# ProProject_TC264__2024-10-06.net
KiCad netlist of a schematic drawn in EasyEDA Pro
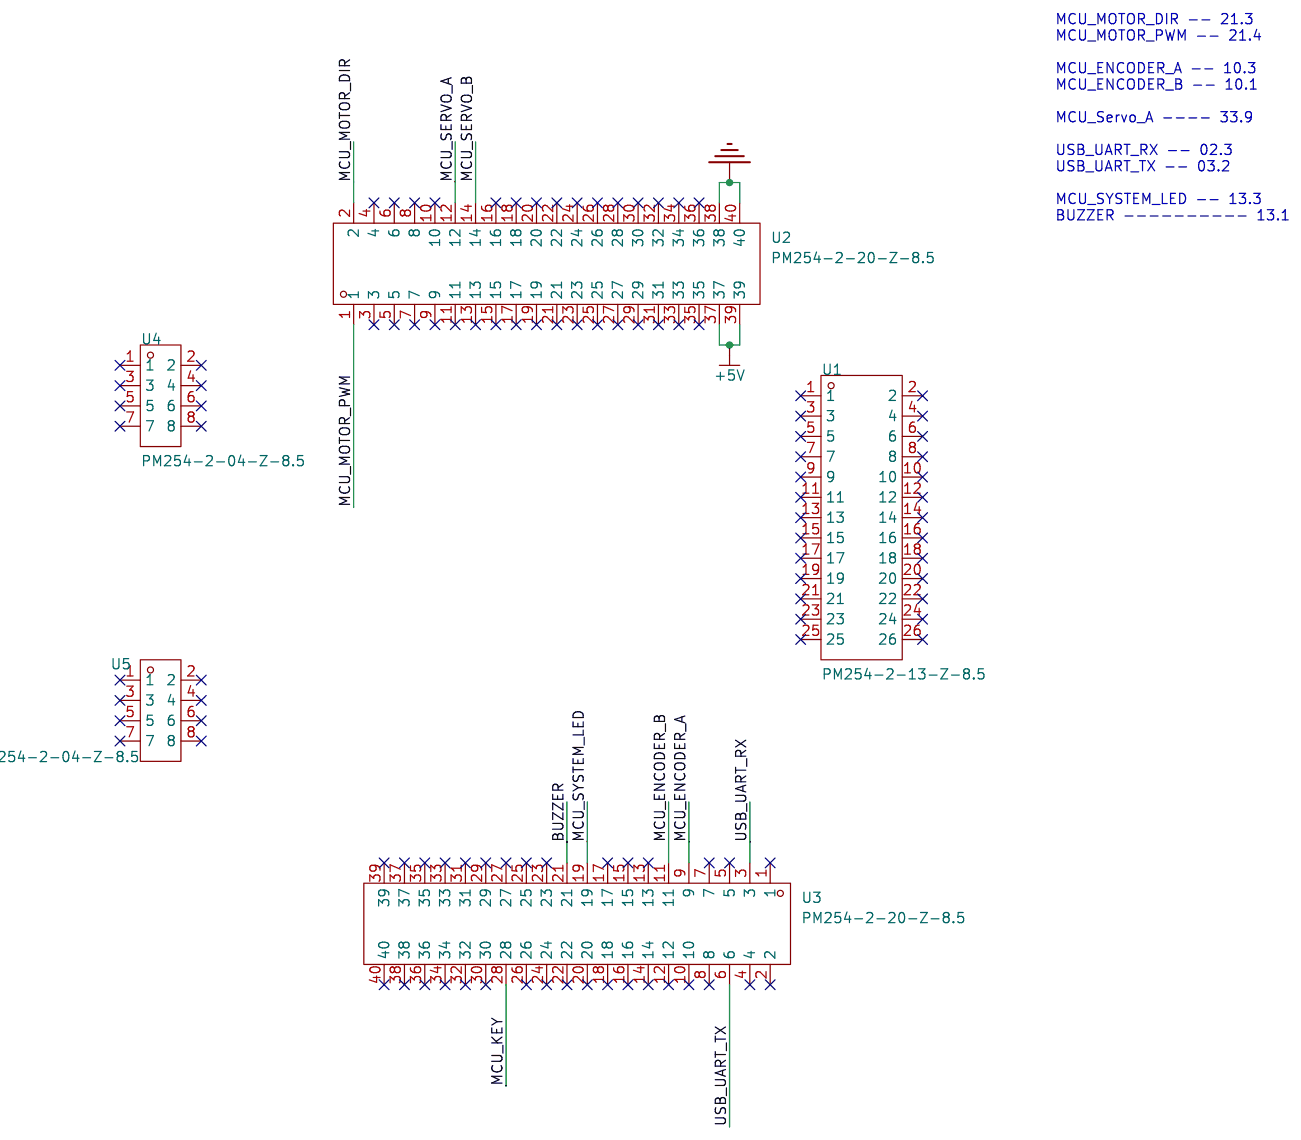
[diagram p0: CoreBoard]
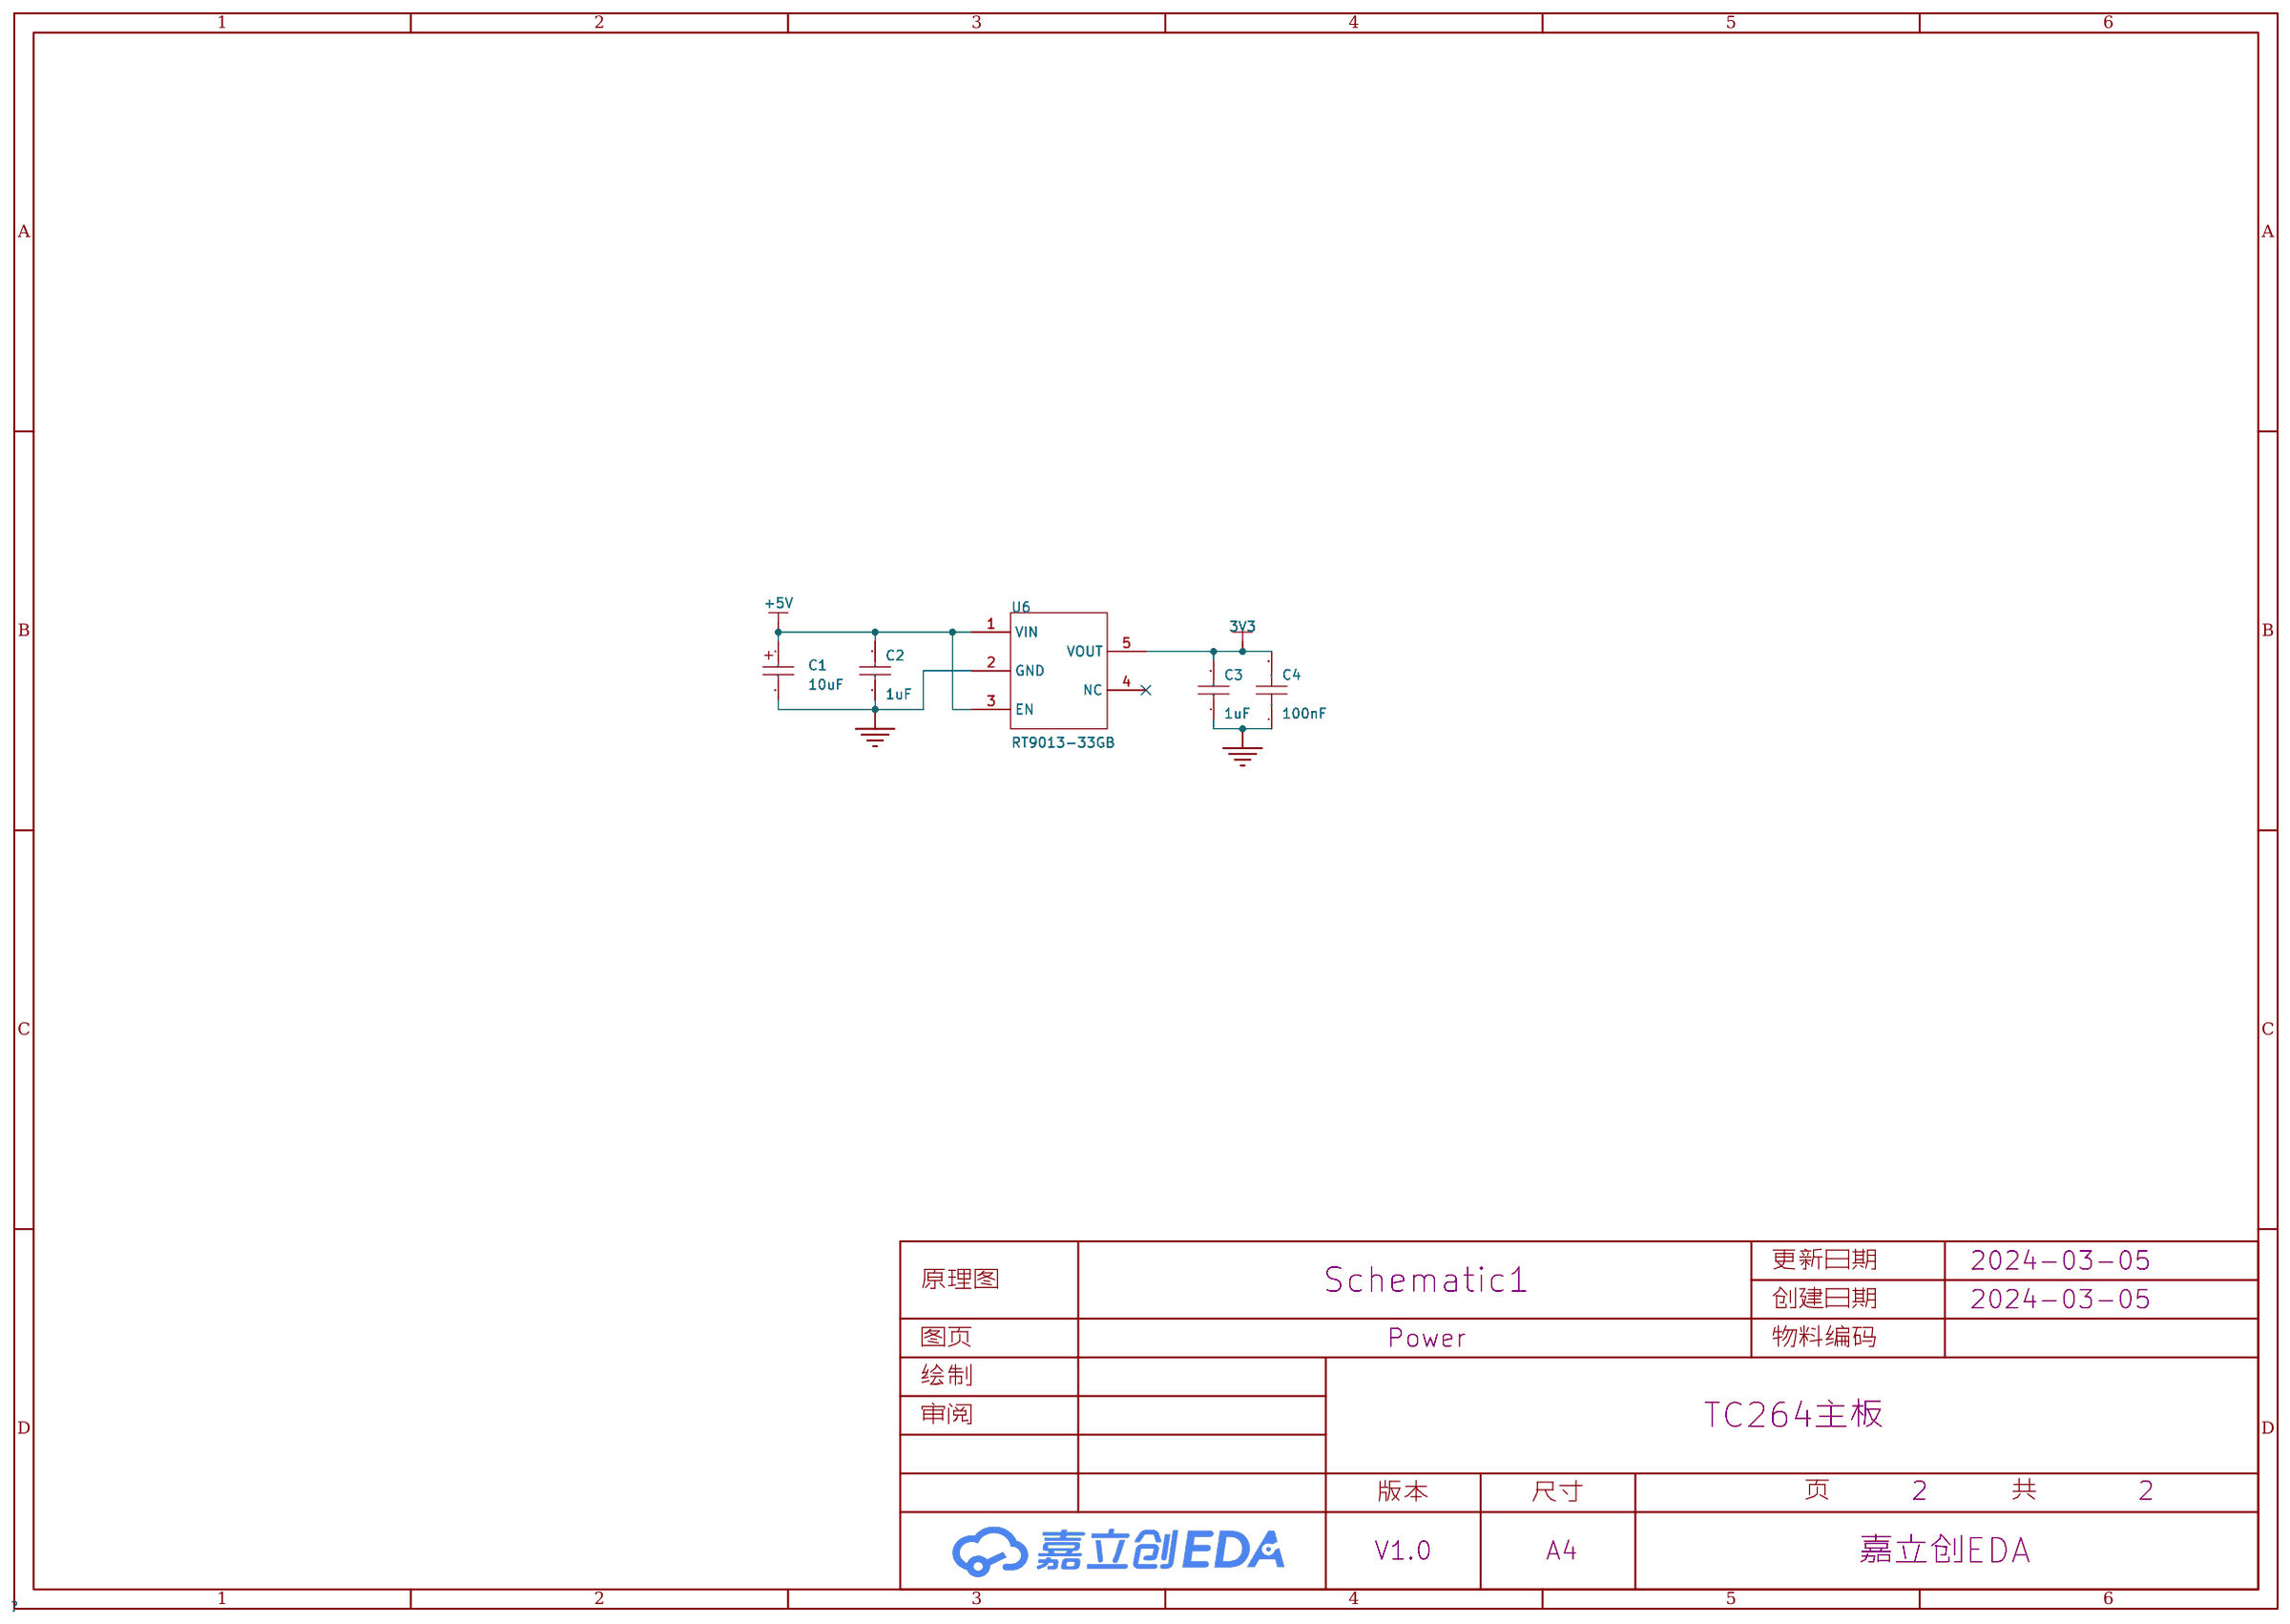
[diagram p1: Power]
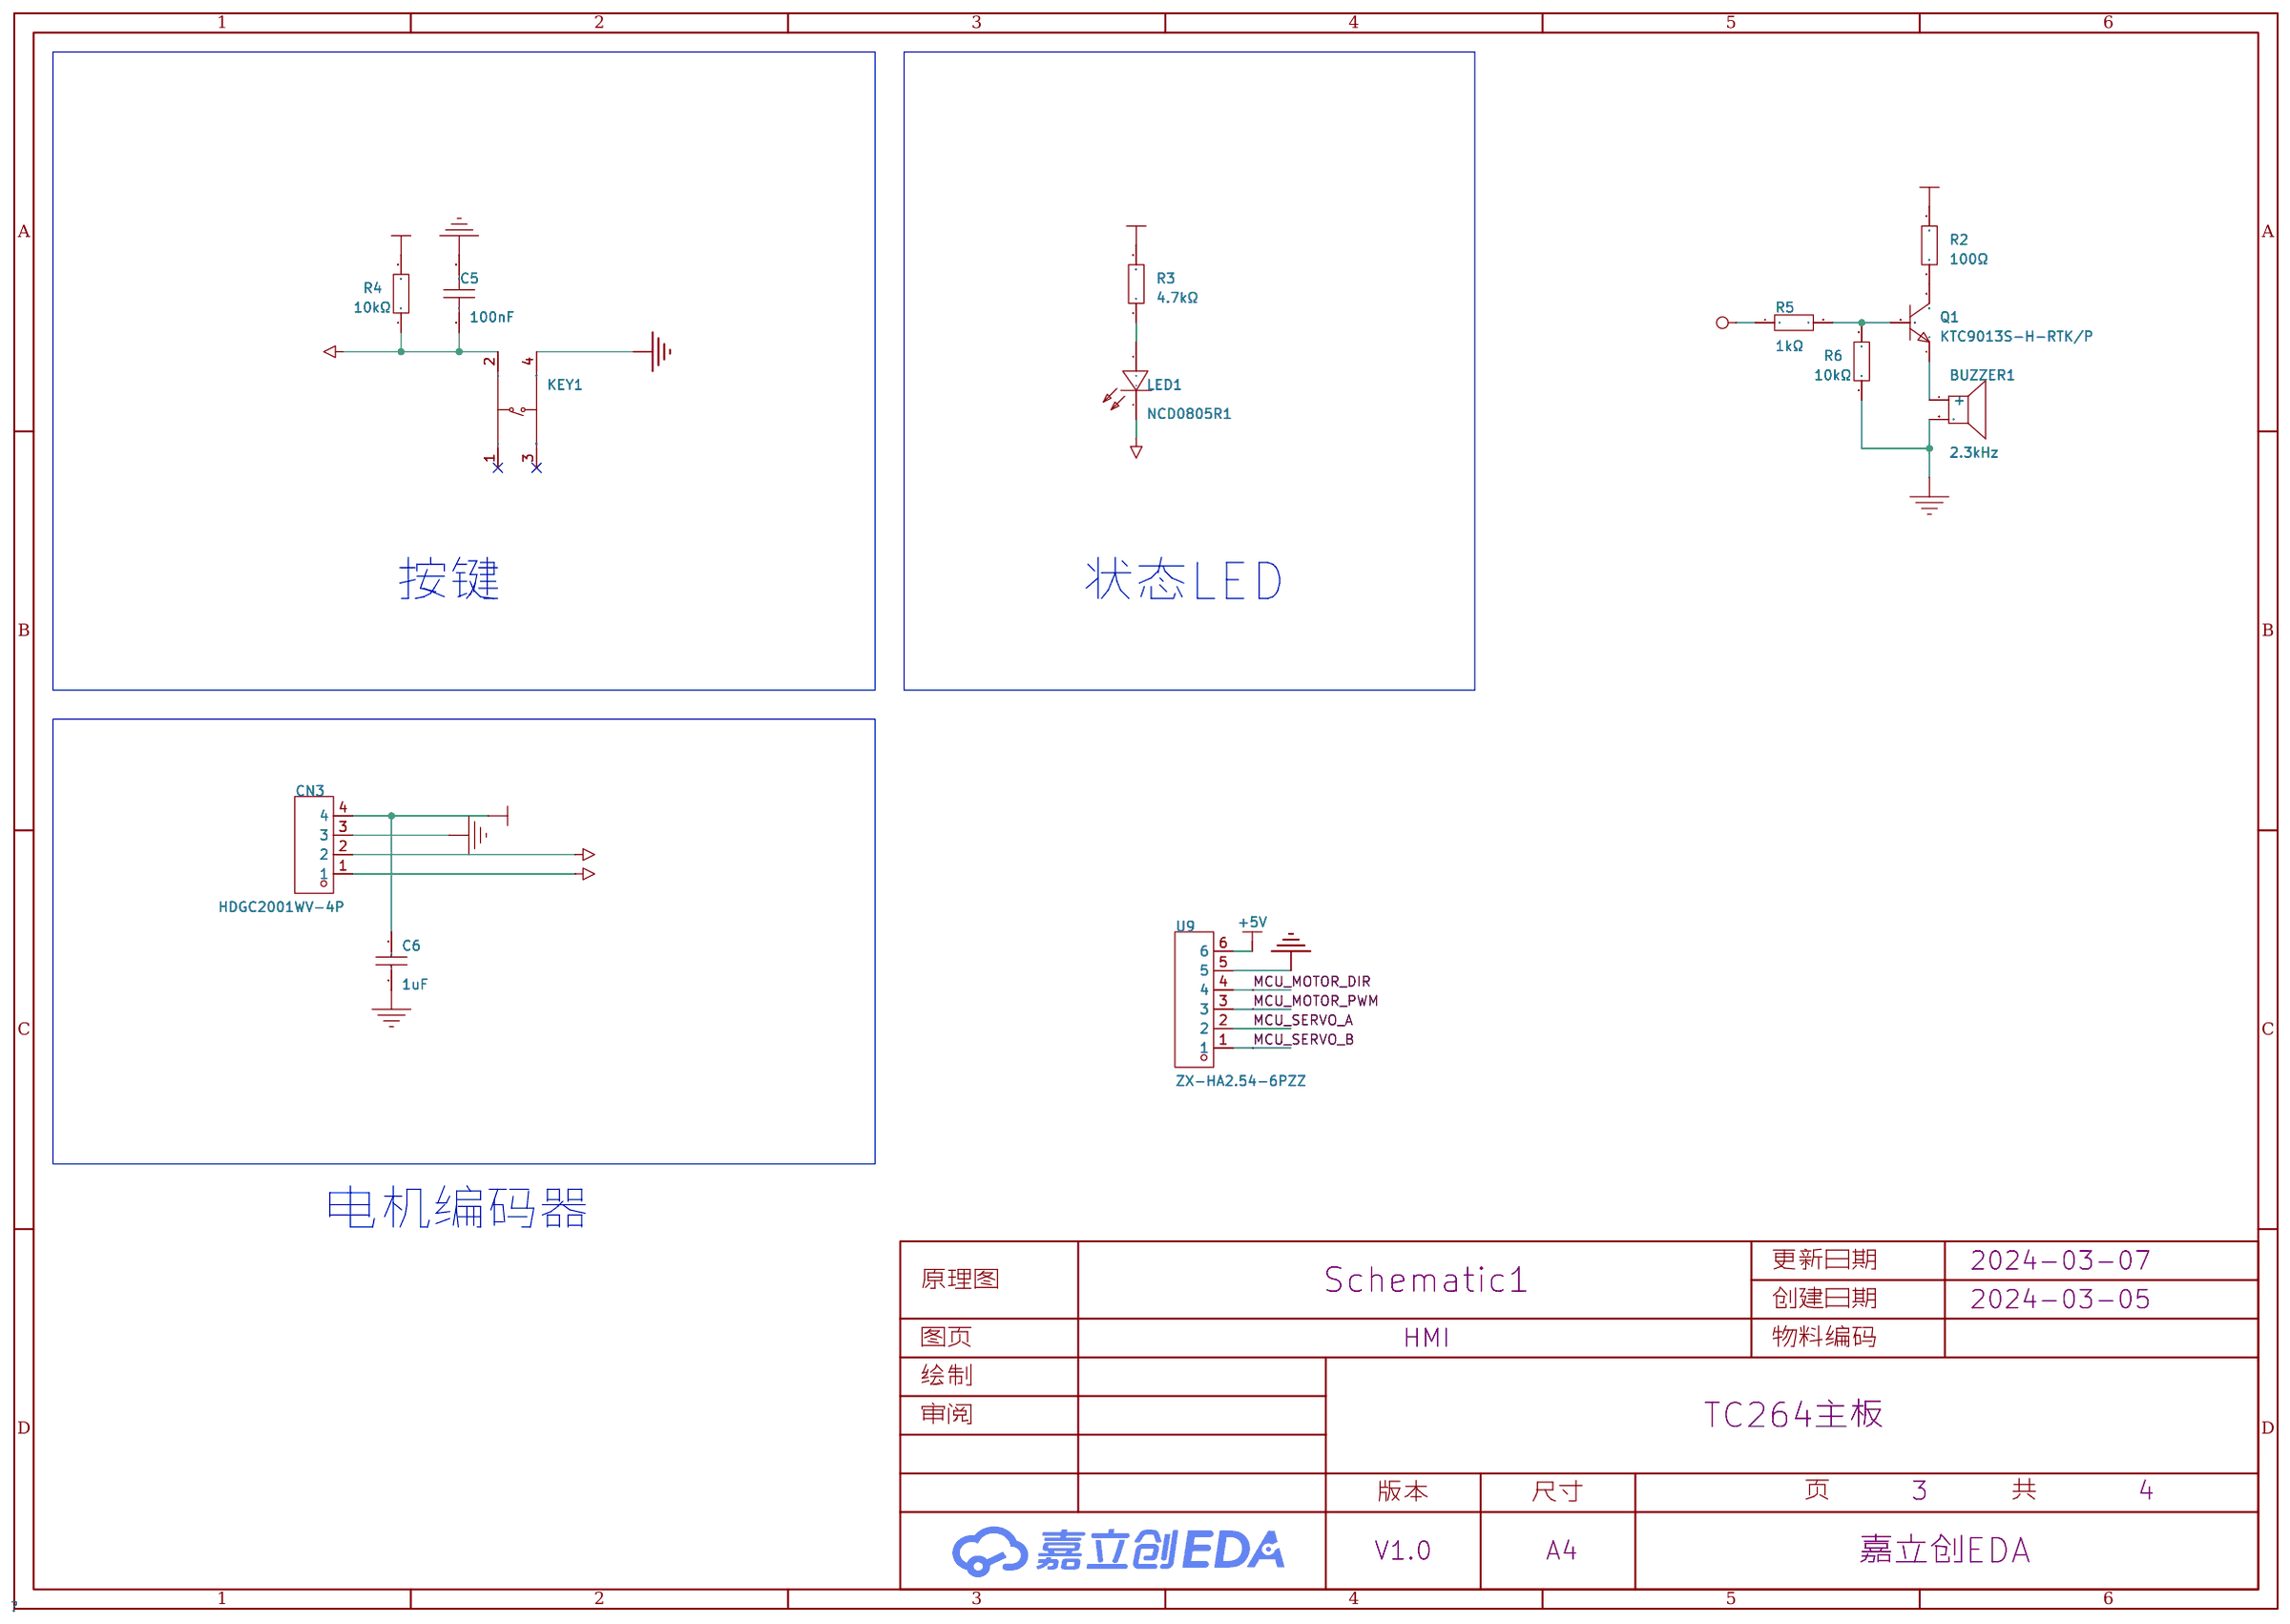
[diagram p2: HMI]
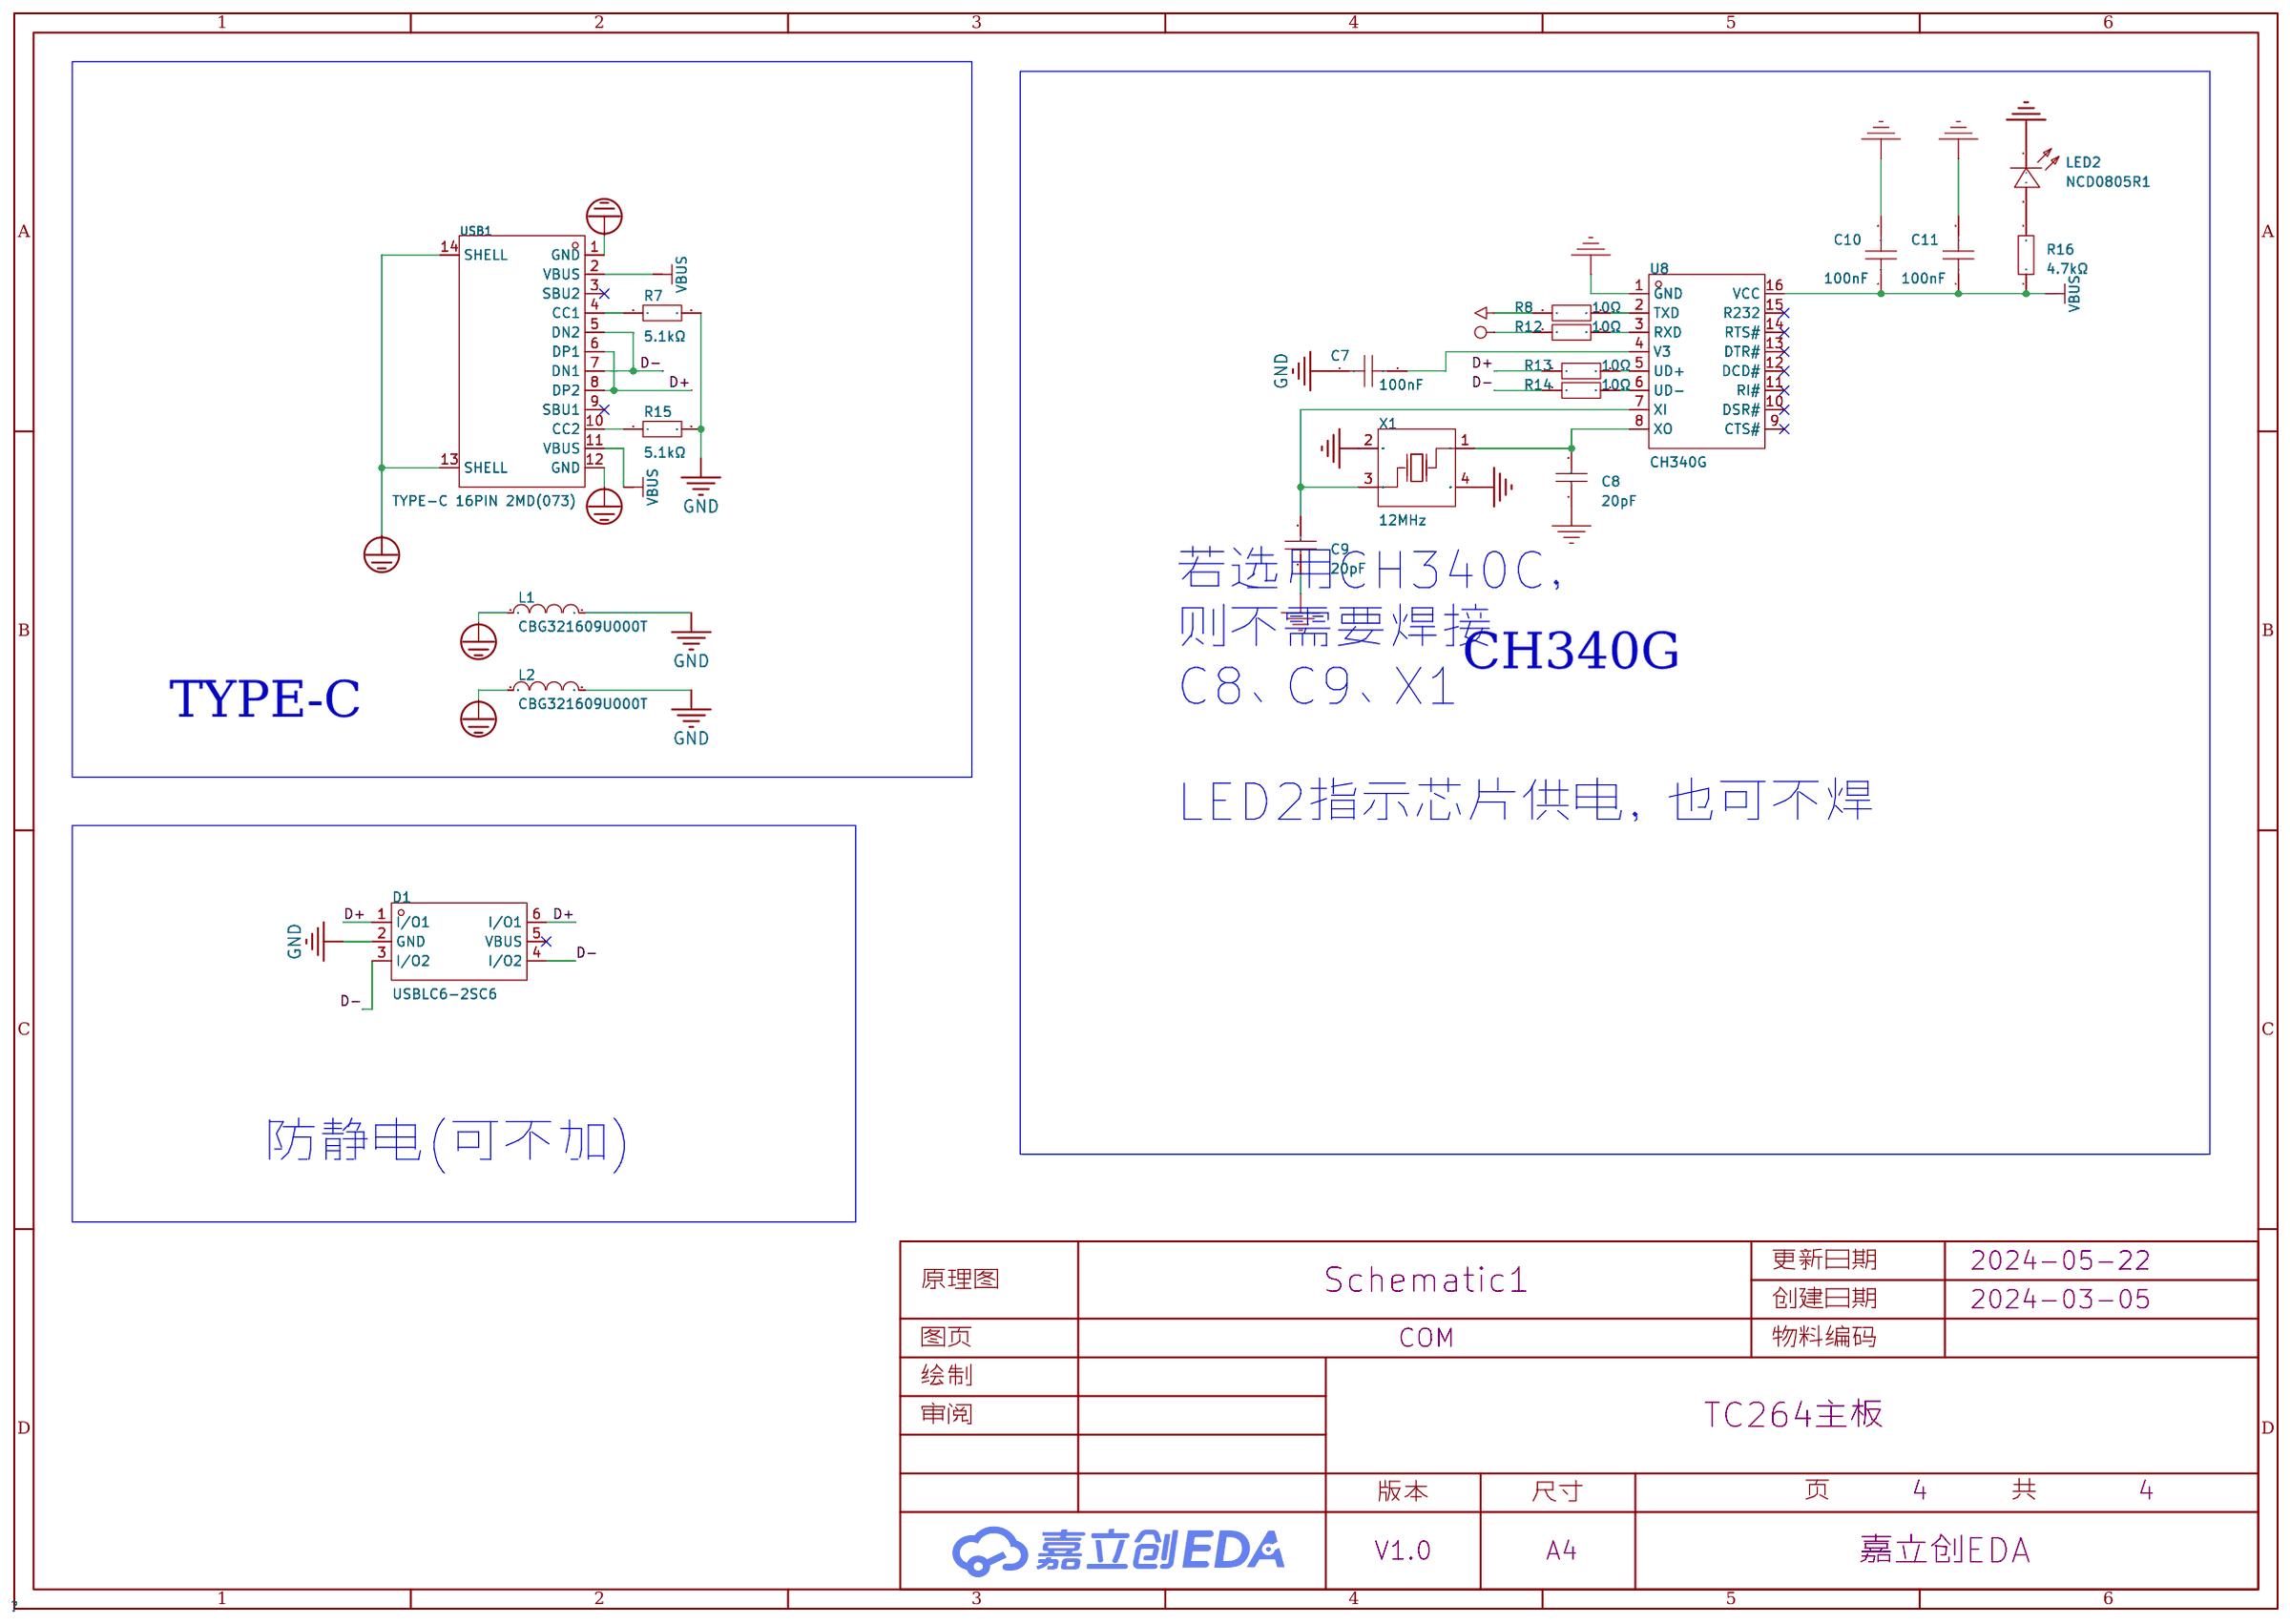
[diagram p3: COM]

(export (version "E")
  (design (tool "Eeschema 10.0.6"))
  (components
    (comp (ref "U1")
      (value "PM254-2-13-Z-8.5")
      (footprint "easyedapro:HDR-TH_26P-P2.54-V-F-R2-C13-S2.54-1")
      (fields (field (name "Manufacturer") "HCTL(华灿天禄)"))
      (libsource (lib "easyedapro") (part "PM254-2-13-Z-8.5"))
    )
    (comp (ref "U2")
      (value "PM254-2-20-Z-8.5")
      (footprint "easyedapro:HDR-TH_40P-P2.54-V-F-R2-C20-S2.54")
      (fields (field (name "Manufacturer") "HCTL(华灿天禄)"))
      (libsource (lib "easyedapro") (part "PM254-2-20-Z-8.5"))
    )
    (comp (ref "U3")
      (value "PM254-2-20-Z-8.5")
      (footprint "easyedapro:HDR-TH_40P-P2.54-V-F-R2-C20-S2.54")
      (fields (field (name "Manufacturer") "HCTL(华灿天禄)"))
      (libsource (lib "easyedapro") (part "PM254-2-20-Z-8.5"))
    )
    (comp (ref "U4")
      (value "PM254-2-04-Z-8.5")
      (footprint "easyedapro:HDR-TH_8P-P2.54-V-F-R2-C4-S2.54")
      (fields (field (name "Manufacturer") "HCTL(华灿天禄)"))
      (libsource (lib "easyedapro") (part "PM254-2-04-Z-8.5"))
    )
    (comp (ref "U5")
      (value "PM254-2-04-Z-8.5")
      (footprint "easyedapro:HDR-TH_8P-P2.54-V-F-R2-C4-S2.54")
      (fields (field (name "Manufacturer") "HCTL(华灿天禄)"))
      (libsource (lib "easyedapro") (part "PM254-2-04-Z-8.5"))
    )
    (comp (ref "C1")
      (value "10uF")
      (footprint "easyedapro:CAP-SMD_L3.2-W1.6-RD-C7171")
      (description "容值:10uF;精度:±10%;额定电压:16V;等效串联电阻:3Ω@100kHz;")
      (fields (field (name "Manufacturer Part") "TAJA106K016RNJ") (field (name "Manufacturer") "Kyocera AVX"))
      (libsource (lib "easyedapro") (part "TAJA106K016RNJ"))
    )
    (comp (ref "C2")
      (value "1uF")
      (footprint "easyedapro:C0603")
      (description "容值:1uF;精度:±10%;额定电压:25V;材质(温度系数):X7R;")
      (fields (field (name "Manufacturer Part") "0603B105K250NT") (field (name "Manufacturer") "FH(风华)"))
      (libsource (lib "easyedapro") (part "0603B105K250NT"))
    )
    (comp (ref "C3")
      (value "1uF")
      (footprint "easyedapro:C0603")
      (description "容值:1uF;精度:±10%;额定电压:25V;材质(温度系数):X7R;")
      (fields (field (name "Manufacturer Part") "0603B105K250NT") (field (name "Manufacturer") "FH(风华)"))
      (libsource (lib "easyedapro") (part "0603B105K250NT"))
    )
    (comp (ref "C4")
      (value "100nF")
      (footprint "easyedapro:C0603")
      (description "容值:100nF;精度:±10%;额定电压:50V;材质(温度系数):X7R;")
      (fields
        (field (name "Manufacturer Part") "CC0603KRX7R9BB104")
        (field (name "Manufacturer") "YAGEO(国巨)")
      )
      (libsource (lib "easyedapro") (part "CC0603KRX7R9BB104"))
    )
    (comp (ref "U6")
      (value "RT9013-33GB")
      (footprint "easyedapro:SOT-23-5_L3.0-W1.7-P0.95-LS2.8-BL")
      (description "输出类型:固定;最大输入电压:5.5V;输出电压:3.3V;最大输出电流:500mA;电源纹波抑制比(PSRR):50dB@(10kHz);输出极性:正极;")
      (fields (field (name "Manufacturer") "RICHTEK(立锜)"))
      (libsource (lib "easyedapro") (part "RT9013-33GB"))
    )
    (comp (ref "BUZZER1")
      (value "2.3kHz")
      (footprint "easyedapro:BUZ-TH_BD12.0-P7.60-D0.6-FD")
      (description "驱动方式:有源(内含驱动线路);构造类型:电磁式;额定电压:5V;频率:2.3kHz;声压(SPL):85dB@5V,10cm;")
      (fields (field (name "Manufacturer Part") "TMB12A05") (field (name "Manufacturer") "华能"))
      (libsource (lib "easyedapro") (part "TMB12A05"))
    )
    (comp (ref "C5")
      (value "100nF")
      (footprint "easyedapro:C0603")
      (description "容值:100nF;精度:±10%;额定电压:50V;材质(温度系数):X7R;")
      (fields
        (field (name "Manufacturer Part") "CC0603KRX7R9BB104")
        (field (name "Manufacturer") "YAGEO(国巨)")
      )
      (libsource (lib "easyedapro") (part "CC0603KRX7R9BB104"))
    )
    (comp (ref "C6")
      (value "1uF")
      (footprint "easyedapro:C0603")
      (description "容值:1uF;精度:±10%;额定电压:25V;材质(温度系数):X7R;")
      (fields (field (name "Manufacturer Part") "0603B105K250NT") (field (name "Manufacturer") "FH(风华)"))
      (libsource (lib "easyedapro") (part "0603B105K250NT"))
    )
    (comp (ref "CN3")
      (value "HDGC2001WV-4P")
      (footprint "easyedapro:CONN-TH_4P-P2.00_HDGC_HDGC2001WV-4P")
      (fields (field (name "Manufacturer") "HDGC(华德共创)"))
      (libsource (lib "easyedapro") (part "HDGC2001WV-4P"))
    )
    (comp (ref "KEY1")
      (value "TS665CJ")
      (footprint "easyedapro:SW-TH_4P-L6.0-W6.0-P4.50-LS6.5")
      (description "触点电流:50mA;额定电压(DC):12V;电路结构:单刀单掷;安装方式:直插;按钮形状:圆形按钮;带灯:-;开关长度:6mm;开关宽度:6mm;开关高度:5mm;")
      (fields (field (name "Manufacturer") "SHOU HAN(首韩)"))
      (libsource (lib "easyedapro") (part "TS665CJ"))
    )
    (comp (ref "LED1")
      (value "NCD0805R1")
      (footprint "easyedapro:LED0805-RD")
      (description "发光颜色:红灯;")
      (fields (field (name "Manufacturer") "国星光电"))
      (libsource (lib "easyedapro") (part "FC-2012HRK-620D"))
    )
    (comp (ref "Q1")
      (value "KTC9013S-H-RTK/P")
      (footprint "easyedapro:SOT-23-3_L2.9-W1.3-P1.90-LS2.4-TR-CW")
      (fields (field (name "Manufacturer") "KEC"))
      (libsource (lib "easyedapro") (part "KTC9013S-H-RTK/P"))
    )
    (comp (ref "R2")
      (value "100Ω")
      (footprint "easyedapro:R0603")
      (description "电阻类型:厚膜电阻;阻值:100Ω;精度:±1%;功率:100mW;温度系数:±200ppm/°C;最大工作电压:75V;工作温度范围:-55°C~+155°C;")
      (fields
        (field (name "Manufacturer Part") "0603WAF1000T5E")
        (field (name "Manufacturer") "UNI-ROYAL(厚声)")
      )
      (libsource (lib "easyedapro") (part "0603WAF1000T5E"))
    )
    (comp (ref "R3")
      (value "4.7kΩ")
      (footprint "easyedapro:R0805")
      (description "阻值:4.7kΩ;精度:±1%;功率:125mW;温度系数:±100ppm/°C;最大工作电压:150V;工作温度范围:-55°C~+155°C;")
      (fields (field (name "Manufacturer Part") "RS-05K4701FT") (field (name "Manufacturer") "FH(风华)"))
      (libsource (lib "easyedapro") (part "RS-05K4701FT"))
    )
    (comp (ref "R4")
      (value "10kΩ")
      (footprint "easyedapro:R0603")
      (description "电阻类型:厚膜电阻;阻值:10kΩ;精度:±1%;功率:100mW;温度系数:±100ppm/°C;最大工作电压:75V;工作温度范围:-55°C~+155°C;")
      (fields
        (field (name "Manufacturer Part") "0603WAF1002T5E")
        (field (name "Manufacturer") "UNI-ROYAL(厚声)")
      )
      (libsource (lib "easyedapro") (part "0603WAF1002T5E"))
    )
    (comp (ref "R5")
      (value "1kΩ")
      (footprint "easyedapro:R0603")
      (description "电阻类型:厚膜电阻;阻值:1kΩ;精度:±1%;功率:100mW;温度系数:±100ppm/°C;最大工作电压:75V;工作温度范围:-55°C~+155°C;")
      (fields
        (field (name "Manufacturer Part") "0603WAF1001T5E")
        (field (name "Manufacturer") "UNI-ROYAL(厚声)")
      )
      (libsource (lib "easyedapro") (part "0603WAF1001T5E"))
    )
    (comp (ref "R6")
      (value "10kΩ")
      (footprint "easyedapro:R0603")
      (description "电阻类型:厚膜电阻;阻值:10kΩ;精度:±1%;功率:100mW;温度系数:±100ppm/°C;最大工作电压:75V;工作温度范围:-55°C~+155°C;")
      (fields
        (field (name "Manufacturer Part") "0603WAF1002T5E")
        (field (name "Manufacturer") "UNI-ROYAL(厚声)")
      )
      (libsource (lib "easyedapro") (part "0603WAF1002T5E"))
    )
    (comp (ref "U9")
      (value "ZX-HA2.54-6PZZ")
      (footprint "easyedapro:CONN-TH_6P-P2.50_ZX-HA2.54-6PZZ")
      (fields (field (name "Manufacturer") "Megastar(兆星)"))
      (libsource (lib "easyedapro") (part "ZX-HA2.54-6PZZ"))
    )
    (comp (ref "C7")
      (value "100nF")
      (footprint "easyedapro:C0603")
      (description "容值:100nF;精度:±10%;额定电压:50V;材质(温度系数):X7R;")
      (fields
        (field (name "Manufacturer Part") "CC0603KRX7R9BB104")
        (field (name "Manufacturer") "YAGEO(国巨)")
      )
      (libsource (lib "easyedapro") (part "CC0603KRX7R9BB104"))
    )
    (comp (ref "C8")
      (value "20pF")
      (footprint "easyedapro:C0603")
      (description "容值:20pF;精度:±5%;额定电压:50V;材质(温度系数):NP0;")
      (fields
        (field (name "Manufacturer Part") "CC0603JRNPO9BN200")
        (field (name "Manufacturer") "YAGEO(国巨)")
      )
      (libsource (lib "easyedapro") (part "CC0603JRNPO9BN200"))
    )
    (comp (ref "C9")
      (value "20pF")
      (footprint "easyedapro:C0603")
      (description "容值:20pF;精度:±5%;额定电压:50V;材质(温度系数):NP0;")
      (fields
        (field (name "Manufacturer Part") "CC0603JRNPO9BN200")
        (field (name "Manufacturer") "YAGEO(国巨)")
      )
      (libsource (lib "easyedapro") (part "CC0603JRNPO9BN200"))
    )
    (comp (ref "C10")
      (value "100nF")
      (footprint "easyedapro:C0603")
      (description "容值:100nF;精度:±10%;额定电压:50V;材质(温度系数):X7R;")
      (fields
        (field (name "Manufacturer Part") "CC0603KRX7R9BB104")
        (field (name "Manufacturer") "YAGEO(国巨)")
      )
      (libsource (lib "easyedapro") (part "CC0603KRX7R9BB104"))
    )
    (comp (ref "C11")
      (value "100nF")
      (footprint "easyedapro:C0603")
      (description "容值:100nF;精度:±10%;额定电压:50V;材质(温度系数):X7R;")
      (fields
        (field (name "Manufacturer Part") "CC0603KRX7R9BB104")
        (field (name "Manufacturer") "YAGEO(国巨)")
      )
      (libsource (lib "easyedapro") (part "CC0603KRX7R9BB104"))
    )
    (comp (ref "D1")
      (value "USBLC6-2SC6")
      (footprint "easyedapro:SOT-23-6_L2.9-W1.6-P0.95-LS2.8-BL")
      (fields (field (name "Manufacturer") "UMW(广东友台半导体)"))
      (libsource (lib "easyedapro") (part "USBLC6-2SC6_C2687116"))
    )
    (comp (ref "L1")
      (value "CBG321609U000T")
      (footprint "easyedapro:L1206")
      (description "标称阻抗@测试频率:0Ω@100MHz;直流电阻(RDC):100mΩ;")
      (fields (field (name "Manufacturer") "FH(风华)"))
      (libsource (lib "easyedapro") (part "CBG321609U000T"))
    )
    (comp (ref "L2")
      (value "CBG321609U000T")
      (footprint "easyedapro:L1206")
      (description "标称阻抗@测试频率:0Ω@100MHz;直流电阻(RDC):100mΩ;")
      (fields (field (name "Manufacturer") "FH(风华)"))
      (libsource (lib "easyedapro") (part "CBG321609U000T"))
    )
    (comp (ref "LED2")
      (value "NCD0805R1")
      (footprint "easyedapro:LED0805-RD")
      (description "发光颜色:红灯;")
      (fields (field (name "Manufacturer") "国星光电"))
      (libsource (lib "easyedapro") (part "FC-2012HRK-620D"))
    )
    (comp (ref "R7")
      (value "5.1kΩ")
      (footprint "easyedapro:R0603")
      (description "电阻类型:厚膜电阻;阻值:5.1kΩ;精度:±1%;功率:100mW;温度系数:±100ppm/°C;最大工作电压:75V;工作温度范围:-55°C~+155°C;")
      (fields
        (field (name "Manufacturer Part") "0603WAF5101T5E")
        (field (name "Manufacturer") "UNI-ROYAL(厚声)")
      )
      (libsource (lib "easyedapro") (part "0603WAF5101T5E"))
    )
    (comp (ref "R8")
      (value "10Ω")
      (footprint "easyedapro:R0603")
      (description "电阻类型:厚膜电阻;阻值:10Ω;精度:±1%;功率:100mW;温度系数:±400ppm/°C;最大工作电压:75V;工作温度范围:-55°C~+155°C;")
      (fields
        (field (name "Manufacturer Part") "0603WAF100JT5E")
        (field (name "Manufacturer") "UNI-ROYAL(厚声)")
      )
      (libsource (lib "easyedapro") (part "0603WAF100JT5E"))
    )
    (comp (ref "R12")
      (value "10Ω")
      (footprint "easyedapro:R0603")
      (description "电阻类型:厚膜电阻;阻值:10Ω;精度:±1%;功率:100mW;温度系数:±400ppm/°C;最大工作电压:75V;工作温度范围:-55°C~+155°C;")
      (fields
        (field (name "Manufacturer Part") "0603WAF100JT5E")
        (field (name "Manufacturer") "UNI-ROYAL(厚声)")
      )
      (libsource (lib "easyedapro") (part "0603WAF100JT5E"))
    )
    (comp (ref "R13")
      (value "10Ω")
      (footprint "easyedapro:R0603")
      (description "电阻类型:厚膜电阻;阻值:10Ω;精度:±1%;功率:100mW;温度系数:±400ppm/°C;最大工作电压:75V;工作温度范围:-55°C~+155°C;")
      (fields
        (field (name "Manufacturer Part") "0603WAF100JT5E")
        (field (name "Manufacturer") "UNI-ROYAL(厚声)")
      )
      (libsource (lib "easyedapro") (part "0603WAF100JT5E"))
    )
    (comp (ref "R14")
      (value "10Ω")
      (footprint "easyedapro:R0603")
      (description "电阻类型:厚膜电阻;阻值:10Ω;精度:±1%;功率:100mW;温度系数:±400ppm/°C;最大工作电压:75V;工作温度范围:-55°C~+155°C;")
      (fields
        (field (name "Manufacturer Part") "0603WAF100JT5E")
        (field (name "Manufacturer") "UNI-ROYAL(厚声)")
      )
      (libsource (lib "easyedapro") (part "0603WAF100JT5E"))
    )
    (comp (ref "R15")
      (value "5.1kΩ")
      (footprint "easyedapro:R0603")
      (description "电阻类型:厚膜电阻;阻值:5.1kΩ;精度:±1%;功率:100mW;温度系数:±100ppm/°C;最大工作电压:75V;工作温度范围:-55°C~+155°C;")
      (fields
        (field (name "Manufacturer Part") "0603WAF5101T5E")
        (field (name "Manufacturer") "UNI-ROYAL(厚声)")
      )
      (libsource (lib "easyedapro") (part "0603WAF5101T5E"))
    )
    (comp (ref "R16")
      (value "4.7kΩ")
      (footprint "easyedapro:R0805")
      (description "阻值:4.7kΩ;精度:±1%;功率:125mW;温度系数:±100ppm/°C;最大工作电压:150V;工作温度范围:-55°C~+155°C;")
      (fields (field (name "Manufacturer Part") "RS-05K4701FT") (field (name "Manufacturer") "FH(风华)"))
      (libsource (lib "easyedapro") (part "RS-05K4701FT"))
    )
    (comp (ref "U8")
      (value "CH340G")
      (footprint "easyedapro:SOIC-16_L9.9-W3.9-P1.27-LS6.0-BL")
      (description "类型:Transceiver;协议类别:USB 2.0;驱动器/接收器数:-;数据速率:2Mbps;")
      (fields (field (name "Manufacturer") "WCH(南京沁恒)"))
      (libsource (lib "easyedapro") (part "CH340G"))
    )
    (comp (ref "USB1")
      (value "TYPE-C 16PIN 2MD(073)")
      (footprint "easyedapro:USB-C-SMD_TYPE-C-6PIN-2MD-073")
      (description "连接器类型:Type-C;标准:-;公母:母座;触点数量:16;端口数量:1;安装方式:卧贴;额定电流 - 电源:5A;工作温度范围:-25°C~+85°C;")
      (fields (field (name "Manufacturer") "SHOU HAN(首韩)"))
      (libsource (lib "easyedapro") (part "TYPE-C 16PIN 2MD(073)"))
    )
    (comp (ref "X1")
      (value "12MHz")
      (footprint "easyedapro:OSC-SMD_4P-L3.2-W2.5-BL")
      (description "晶振类型:贴片无源晶振;频率:12MHz;频率公差:±10ppm;频率稳定度:±30ppm;负载电容:20pF;工作温度:-40°C~+85°C;")
      (fields (field (name "Manufacturer Part") "X322512MSB4SI") (field (name "Manufacturer") "YXC(扬兴晶振)"))
      (libsource (lib "easyedapro") (part "X322512MSB4SI"))
    )
  )
  (nets
    (net (code "1") (name "+5V") (class "Default")
      (node (ref "C1") (pin "1") (pinfunction "1_1") (pintype "input"))
      (node (ref "C2") (pin "2") (pinfunction "2_2") (pintype "input"))
      (node (ref "C6") (pin "2") (pinfunction "2_2") (pintype "input"))
      (node (ref "CN3") (pin "4") (pinfunction "4_4") (pintype "input"))
      (node (ref "R2") (pin "2") (pinfunction "2_2") (pintype "input"))
      (node (ref "U2") (pin "37") (pinfunction "37_37") (pintype "unspecified"))
      (node (ref "U2") (pin "39") (pinfunction "39_39") (pintype "unspecified"))
      (node (ref "U6") (pin "1") (pinfunction "VIN_1") (pintype "unspecified"))
      (node (ref "U6") (pin "3") (pinfunction "EN_3") (pintype "unspecified"))
      (node (ref "U9") (pin "6") (pinfunction "6_6") (pintype "unspecified"))
    )
    (net (code "2") (name "3V3") (class "Default")
      (node (ref "C3") (pin "2") (pinfunction "2_2") (pintype "input"))
      (node (ref "C4") (pin "2") (pinfunction "2_2") (pintype "unspecified"))
      (node (ref "R3") (pin "2") (pinfunction "2_2") (pintype "input"))
      (node (ref "R4") (pin "2") (pinfunction "2_2") (pintype "input"))
      (node (ref "U6") (pin "5") (pinfunction "VOUT_5") (pintype "unspecified"))
    )
    (net (code "3") (name "BUZZER") (class "Default")
      (node (ref "R5") (pin "1") (pinfunction "1_1") (pintype "input"))
      (node (ref "U3") (pin "21") (pinfunction "21_21") (pintype "unspecified"))
    )
    (net (code "4") (name "D+") (class "Default")
      (node (ref "D1") (pin "1") (pinfunction "I/O1_1") (pintype "input"))
      (node (ref "D1") (pin "6") (pinfunction "I/O1_6") (pintype "input"))
      (node (ref "R13") (pin "1") (pinfunction "1_1") (pintype "input"))
      (node (ref "USB1") (pin "6") (pinfunction "DP1_6") (pintype "input"))
      (node (ref "USB1") (pin "8") (pinfunction "DP2_8") (pintype "input"))
    )
    (net (code "5") (name "D-") (class "Default")
      (node (ref "D1") (pin "3") (pinfunction "I/O2_3") (pintype "input"))
      (node (ref "D1") (pin "4") (pinfunction "I/O2_4") (pintype "input"))
      (node (ref "R14") (pin "1") (pinfunction "1_1") (pintype "input"))
      (node (ref "USB1") (pin "5") (pinfunction "DN2_5") (pintype "input"))
      (node (ref "USB1") (pin "7") (pinfunction "DN1_7") (pintype "input"))
    )
    (net (code "6") (name "GND") (class "Default")
      (node (ref "BUZZER1") (pin "2") (pinfunction "2_2") (pintype "input"))
      (node (ref "C1") (pin "2") (pinfunction "2_2") (pintype "input"))
      (node (ref "C10") (pin "2") (pinfunction "2_2") (pintype "unspecified"))
      (node (ref "C11") (pin "2") (pinfunction "2_2") (pintype "unspecified"))
      (node (ref "C2") (pin "1") (pinfunction "1_1") (pintype "input"))
      (node (ref "C3") (pin "1") (pinfunction "1_1") (pintype "input"))
      (node (ref "C4") (pin "1") (pinfunction "1_1") (pintype "unspecified"))
      (node (ref "C5") (pin "2") (pinfunction "2_2") (pintype "unspecified"))
      (node (ref "C6") (pin "1") (pinfunction "1_1") (pintype "input"))
      (node (ref "C7") (pin "1") (pinfunction "1_1") (pintype "unspecified"))
      (node (ref "C8") (pin "1") (pinfunction "1_1") (pintype "input"))
      (node (ref "C9") (pin "1") (pinfunction "1_1") (pintype "input"))
      (node (ref "CN3") (pin "3") (pinfunction "3_3") (pintype "input"))
      (node (ref "D1") (pin "2") (pinfunction "GND_2") (pintype "input"))
      (node (ref "KEY1") (pin "4") (pinfunction "D_4") (pintype "input"))
      (node (ref "L1") (pin "2") (pinfunction "2_2") (pintype "unspecified"))
      (node (ref "L2") (pin "2") (pinfunction "2_2") (pintype "unspecified"))
      (node (ref "LED2") (pin "1") (pinfunction "-_1") (pintype "input"))
      (node (ref "R15") (pin "2") (pinfunction "2_2") (pintype "input"))
      (node (ref "R6") (pin "1") (pinfunction "1_1") (pintype "input"))
      (node (ref "R7") (pin "2") (pinfunction "2_2") (pintype "input"))
      (node (ref "U2") (pin "38") (pinfunction "38_38") (pintype "unspecified"))
      (node (ref "U2") (pin "40") (pinfunction "40_40") (pintype "unspecified"))
      (node (ref "U6") (pin "2") (pinfunction "GND_2") (pintype "unspecified"))
      (node (ref "U8") (pin "1") (pinfunction "GND_1") (pintype "input"))
      (node (ref "U9") (pin "5") (pinfunction "5_5") (pintype "unspecified"))
      (node (ref "X1") (pin "2") (pinfunction "GND_2") (pintype "input"))
      (node (ref "X1") (pin "4") (pinfunction "GND_4") (pintype "input"))
    )
    (net (code "7") (name "MCU_ENCODER_A") (class "Default")
      (node (ref "CN3") (pin "2") (pinfunction "2_2") (pintype "input"))
      (node (ref "U3") (pin "9") (pinfunction "9_9") (pintype "unspecified"))
    )
    (net (code "8") (name "MCU_ENCODER_B") (class "Default")
      (node (ref "CN3") (pin "1") (pinfunction "1_1") (pintype "input"))
      (node (ref "U3") (pin "11") (pinfunction "11_11") (pintype "unspecified"))
    )
    (net (code "9") (name "MCU_KEY") (class "Default")
      (node (ref "C5") (pin "1") (pinfunction "1_1") (pintype "unspecified"))
      (node (ref "KEY1") (pin "2") (pinfunction "B_2") (pintype "input"))
      (node (ref "R4") (pin "1") (pinfunction "1_1") (pintype "input"))
      (node (ref "U3") (pin "28") (pinfunction "28_28") (pintype "unspecified"))
    )
    (net (code "10") (name "MCU_MOTOR_DIR") (class "Default")
      (node (ref "U2") (pin "2") (pinfunction "2_2") (pintype "unspecified"))
      (node (ref "U9") (pin "4") (pinfunction "4_4") (pintype "unspecified"))
    )
    (net (code "11") (name "MCU_MOTOR_PWM") (class "Default")
      (node (ref "U2") (pin "1") (pinfunction "1_1") (pintype "unspecified"))
      (node (ref "U9") (pin "3") (pinfunction "3_3") (pintype "unspecified"))
    )
    (net (code "12") (name "MCU_SERVO_A") (class "Default")
      (node (ref "U2") (pin "12") (pinfunction "12_12") (pintype "unspecified"))
      (node (ref "U9") (pin "2") (pinfunction "2_2") (pintype "unspecified"))
    )
    (net (code "13") (name "MCU_SERVO_B") (class "Default")
      (node (ref "U2") (pin "14") (pinfunction "14_14") (pintype "unspecified"))
      (node (ref "U9") (pin "1") (pinfunction "1_1") (pintype "unspecified"))
    )
    (net (code "14") (name "MCU_SYSTEM_LED") (class "Default")
      (node (ref "LED1") (pin "1") (pinfunction "-_1") (pintype "input"))
      (node (ref "U3") (pin "19") (pinfunction "19_19") (pintype "unspecified"))
    )
    (net (code "15") (name "Net-(BUZZER1-+)") (class "Default")
      (node (ref "BUZZER1") (pin "1") (pinfunction "+_1") (pintype "input"))
      (node (ref "Q1") (pin "1") (pinfunction "E_1") (pintype "input"))
    )
    (net (code "16") (name "Net-(LED1-+)") (class "Default")
      (node (ref "LED1") (pin "2") (pinfunction "+_2") (pintype "input"))
      (node (ref "R3") (pin "1") (pinfunction "1_1") (pintype "input"))
    )
    (net (code "17") (name "Net-(LED2-+)") (class "Default")
      (node (ref "LED2") (pin "2") (pinfunction "+_2") (pintype "input"))
      (node (ref "R16") (pin "2") (pinfunction "2_2") (pintype "input"))
    )
    (net (code "18") (name "Net-(Q1-B)") (class "Default")
      (node (ref "Q1") (pin "2") (pinfunction "B_2") (pintype "input"))
      (node (ref "R5") (pin "2") (pinfunction "2_2") (pintype "input"))
      (node (ref "R6") (pin "2") (pinfunction "2_2") (pintype "input"))
    )
    (net (code "19") (name "Net-(Q1-C)") (class "Default")
      (node (ref "Q1") (pin "3") (pinfunction "C_3") (pintype "input"))
      (node (ref "R2") (pin "1") (pinfunction "1_1") (pintype "input"))
    )
    (net (code "20") (name "Net-(U8-RXD)") (class "Default")
      (node (ref "R12") (pin "2") (pinfunction "2_2") (pintype "input"))
      (node (ref "U8") (pin "3") (pinfunction "RXD_3") (pintype "input"))
    )
    (net (code "21") (name "Net-(U8-TXD)") (class "Default")
      (node (ref "R8") (pin "2") (pinfunction "2_2") (pintype "input"))
      (node (ref "U8") (pin "2") (pinfunction "TXD_2") (pintype "input"))
    )
    (net (code "22") (name "Net-(U8-UD+)") (class "Default")
      (node (ref "R13") (pin "2") (pinfunction "2_2") (pintype "input"))
      (node (ref "U8") (pin "5") (pinfunction "UD+_5") (pintype "input"))
    )
    (net (code "23") (name "Net-(U8-UD-)") (class "Default")
      (node (ref "R14") (pin "2") (pinfunction "2_2") (pintype "input"))
      (node (ref "U8") (pin "6") (pinfunction "UD-_6") (pintype "input"))
    )
    (net (code "24") (name "Net-(U8-V3)") (class "Default")
      (node (ref "C7") (pin "2") (pinfunction "2_2") (pintype "unspecified"))
      (node (ref "U8") (pin "4") (pinfunction "V3_4") (pintype "input"))
    )
    (net (code "25") (name "Net-(U8-XI)") (class "Default")
      (node (ref "C9") (pin "2") (pinfunction "2_2") (pintype "input"))
      (node (ref "U8") (pin "7") (pinfunction "XI_7") (pintype "input"))
      (node (ref "X1") (pin "3") (pinfunction "OSC2_3") (pintype "input"))
    )
    (net (code "26") (name "Net-(U8-XO)") (class "Default")
      (node (ref "C8") (pin "2") (pinfunction "2_2") (pintype "input"))
      (node (ref "U8") (pin "8") (pinfunction "XO_8") (pintype "input"))
      (node (ref "X1") (pin "1") (pinfunction "OSC1_1") (pintype "input"))
    )
    (net (code "27") (name "Net-(USB1-CC1)") (class "Default")
      (node (ref "R7") (pin "1") (pinfunction "1_1") (pintype "input"))
      (node (ref "USB1") (pin "4") (pinfunction "CC1_4") (pintype "input"))
    )
    (net (code "28") (name "Net-(USB1-CC2)") (class "Default")
      (node (ref "R15") (pin "1") (pinfunction "1_1") (pintype "input"))
      (node (ref "USB1") (pin "10") (pinfunction "CC2_10") (pintype "input"))
    )
    (net (code "29") (name "PGND") (class "Default")
      (node (ref "L1") (pin "1") (pinfunction "1_1") (pintype "unspecified"))
      (node (ref "L2") (pin "1") (pinfunction "1_1") (pintype "unspecified"))
      (node (ref "USB1") (pin "1") (pinfunction "GND_1") (pintype "input"))
      (node (ref "USB1") (pin "12") (pinfunction "GND_12") (pintype "input"))
      (node (ref "USB1") (pin "13") (pinfunction "SHELL_13") (pintype "input"))
      (node (ref "USB1") (pin "14") (pinfunction "SHELL_14") (pintype "input"))
    )
    (net (code "30") (name "USB_UART_RX") (class "Default")
      (node (ref "R8") (pin "1") (pinfunction "1_1") (pintype "input"))
      (node (ref "U3") (pin "3") (pinfunction "3_3") (pintype "unspecified"))
    )
    (net (code "31") (name "USB_UART_TX") (class "Default")
      (node (ref "R12") (pin "1") (pinfunction "1_1") (pintype "input"))
      (node (ref "U3") (pin "6") (pinfunction "6_6") (pintype "unspecified"))
    )
    (net (code "32") (name "VBUS") (class "Default")
      (node (ref "C10") (pin "1") (pinfunction "1_1") (pintype "unspecified"))
      (node (ref "C11") (pin "1") (pinfunction "1_1") (pintype "unspecified"))
      (node (ref "R16") (pin "1") (pinfunction "1_1") (pintype "input"))
      (node (ref "U8") (pin "16") (pinfunction "VCC_16") (pintype "input"))
      (node (ref "USB1") (pin "11") (pinfunction "VBUS_11") (pintype "input"))
      (node (ref "USB1") (pin "2") (pinfunction "VBUS_2") (pintype "input"))
    )
    (net (code "33") (name "unconnected-(D1-VBUS-Pad5)") (class "Default")
      (node (ref "D1") (pin "5") (pinfunction "VBUS_5") (pintype "input+no_connect"))
    )
    (net (code "34") (name "unconnected-(KEY1-A-Pad1)") (class "Default")
      (node (ref "KEY1") (pin "1") (pinfunction "A_1") (pintype "input+no_connect"))
    )
    (net (code "35") (name "unconnected-(KEY1-C-Pad3)") (class "Default")
      (node (ref "KEY1") (pin "3") (pinfunction "C_3") (pintype "input+no_connect"))
    )
    (net (code "36") (name "unconnected-(U1-Pad1)") (class "Default")
      (node (ref "U1") (pin "1") (pinfunction "1_1") (pintype "unspecified+no_connect"))
    )
    (net (code "37") (name "unconnected-(U1-Pad2)") (class "Default")
      (node (ref "U1") (pin "2") (pinfunction "2_2") (pintype "unspecified+no_connect"))
    )
    (net (code "38") (name "unconnected-(U1-Pad3)") (class "Default")
      (node (ref "U1") (pin "3") (pinfunction "3_3") (pintype "unspecified+no_connect"))
    )
    (net (code "39") (name "unconnected-(U1-Pad4)") (class "Default")
      (node (ref "U1") (pin "4") (pinfunction "4_4") (pintype "unspecified+no_connect"))
    )
    (net (code "40") (name "unconnected-(U1-Pad5)") (class "Default")
      (node (ref "U1") (pin "5") (pinfunction "5_5") (pintype "unspecified+no_connect"))
    )
    (net (code "41") (name "unconnected-(U1-Pad6)") (class "Default")
      (node (ref "U1") (pin "6") (pinfunction "6_6") (pintype "unspecified+no_connect"))
    )
    (net (code "42") (name "unconnected-(U1-Pad7)") (class "Default")
      (node (ref "U1") (pin "7") (pinfunction "7_7") (pintype "unspecified+no_connect"))
    )
    (net (code "43") (name "unconnected-(U1-Pad8)") (class "Default")
      (node (ref "U1") (pin "8") (pinfunction "8_8") (pintype "unspecified+no_connect"))
    )
    (net (code "44") (name "unconnected-(U1-Pad9)") (class "Default")
      (node (ref "U1") (pin "9") (pinfunction "9_9") (pintype "unspecified+no_connect"))
    )
    (net (code "45") (name "unconnected-(U1-Pad10)") (class "Default")
      (node (ref "U1") (pin "10") (pinfunction "10_10") (pintype "unspecified+no_connect"))
    )
    (net (code "46") (name "unconnected-(U1-Pad11)") (class "Default")
      (node (ref "U1") (pin "11") (pinfunction "11_11") (pintype "unspecified+no_connect"))
    )
    (net (code "47") (name "unconnected-(U1-Pad12)") (class "Default")
      (node (ref "U1") (pin "12") (pinfunction "12_12") (pintype "unspecified+no_connect"))
    )
    (net (code "48") (name "unconnected-(U1-Pad13)") (class "Default")
      (node (ref "U1") (pin "13") (pinfunction "13_13") (pintype "unspecified+no_connect"))
    )
    (net (code "49") (name "unconnected-(U1-Pad14)") (class "Default")
      (node (ref "U1") (pin "14") (pinfunction "14_14") (pintype "unspecified+no_connect"))
    )
    (net (code "50") (name "unconnected-(U1-Pad15)") (class "Default")
      (node (ref "U1") (pin "15") (pinfunction "15_15") (pintype "unspecified+no_connect"))
    )
    (net (code "51") (name "unconnected-(U1-Pad16)") (class "Default")
      (node (ref "U1") (pin "16") (pinfunction "16_16") (pintype "unspecified+no_connect"))
    )
    (net (code "52") (name "unconnected-(U1-Pad17)") (class "Default")
      (node (ref "U1") (pin "17") (pinfunction "17_17") (pintype "unspecified+no_connect"))
    )
    (net (code "53") (name "unconnected-(U1-Pad18)") (class "Default")
      (node (ref "U1") (pin "18") (pinfunction "18_18") (pintype "unspecified+no_connect"))
    )
    (net (code "54") (name "unconnected-(U1-Pad19)") (class "Default")
      (node (ref "U1") (pin "19") (pinfunction "19_19") (pintype "unspecified+no_connect"))
    )
    (net (code "55") (name "unconnected-(U1-Pad20)") (class "Default")
      (node (ref "U1") (pin "20") (pinfunction "20_20") (pintype "unspecified+no_connect"))
    )
    (net (code "56") (name "unconnected-(U1-Pad21)") (class "Default")
      (node (ref "U1") (pin "21") (pinfunction "21_21") (pintype "unspecified+no_connect"))
    )
    (net (code "57") (name "unconnected-(U1-Pad22)") (class "Default")
      (node (ref "U1") (pin "22") (pinfunction "22_22") (pintype "unspecified+no_connect"))
    )
    (net (code "58") (name "unconnected-(U1-Pad23)") (class "Default")
      (node (ref "U1") (pin "23") (pinfunction "23_23") (pintype "unspecified+no_connect"))
    )
    (net (code "59") (name "unconnected-(U1-Pad24)") (class "Default")
      (node (ref "U1") (pin "24") (pinfunction "24_24") (pintype "unspecified+no_connect"))
    )
    (net (code "60") (name "unconnected-(U1-Pad25)") (class "Default")
      (node (ref "U1") (pin "25") (pinfunction "25_25") (pintype "unspecified+no_connect"))
    )
    (net (code "61") (name "unconnected-(U1-Pad26)") (class "Default")
      (node (ref "U1") (pin "26") (pinfunction "26_26") (pintype "unspecified+no_connect"))
    )
    (net (code "62") (name "unconnected-(U2-Pad3)") (class "Default")
      (node (ref "U2") (pin "3") (pinfunction "3_3") (pintype "unspecified+no_connect"))
    )
    (net (code "63") (name "unconnected-(U2-Pad4)") (class "Default")
      (node (ref "U2") (pin "4") (pinfunction "4_4") (pintype "unspecified+no_connect"))
    )
    (net (code "64") (name "unconnected-(U2-Pad5)") (class "Default")
      (node (ref "U2") (pin "5") (pinfunction "5_5") (pintype "unspecified+no_connect"))
    )
    (net (code "65") (name "unconnected-(U2-Pad6)") (class "Default")
      (node (ref "U2") (pin "6") (pinfunction "6_6") (pintype "unspecified+no_connect"))
    )
    (net (code "66") (name "unconnected-(U2-Pad7)") (class "Default")
      (node (ref "U2") (pin "7") (pinfunction "7_7") (pintype "unspecified+no_connect"))
    )
    (net (code "67") (name "unconnected-(U2-Pad8)") (class "Default")
      (node (ref "U2") (pin "8") (pinfunction "8_8") (pintype "unspecified+no_connect"))
    )
    (net (code "68") (name "unconnected-(U2-Pad9)") (class "Default")
      (node (ref "U2") (pin "9") (pinfunction "9_9") (pintype "unspecified+no_connect"))
    )
    (net (code "69") (name "unconnected-(U2-Pad10)") (class "Default")
      (node (ref "U2") (pin "10") (pinfunction "10_10") (pintype "unspecified+no_connect"))
    )
    (net (code "70") (name "unconnected-(U2-Pad11)") (class "Default")
      (node (ref "U2") (pin "11") (pinfunction "11_11") (pintype "unspecified+no_connect"))
    )
    (net (code "71") (name "unconnected-(U2-Pad13)") (class "Default")
      (node (ref "U2") (pin "13") (pinfunction "13_13") (pintype "unspecified+no_connect"))
    )
    (net (code "72") (name "unconnected-(U2-Pad15)") (class "Default")
      (node (ref "U2") (pin "15") (pinfunction "15_15") (pintype "unspecified+no_connect"))
    )
    (net (code "73") (name "unconnected-(U2-Pad16)") (class "Default")
      (node (ref "U2") (pin "16") (pinfunction "16_16") (pintype "unspecified+no_connect"))
    )
    (net (code "74") (name "unconnected-(U2-Pad17)") (class "Default")
      (node (ref "U2") (pin "17") (pinfunction "17_17") (pintype "unspecified+no_connect"))
    )
    (net (code "75") (name "unconnected-(U2-Pad18)") (class "Default")
      (node (ref "U2") (pin "18") (pinfunction "18_18") (pintype "unspecified+no_connect"))
    )
    (net (code "76") (name "unconnected-(U2-Pad19)") (class "Default")
      (node (ref "U2") (pin "19") (pinfunction "19_19") (pintype "unspecified+no_connect"))
    )
    (net (code "77") (name "unconnected-(U2-Pad20)") (class "Default")
      (node (ref "U2") (pin "20") (pinfunction "20_20") (pintype "unspecified+no_connect"))
    )
    (net (code "78") (name "unconnected-(U2-Pad21)") (class "Default")
      (node (ref "U2") (pin "21") (pinfunction "21_21") (pintype "unspecified+no_connect"))
    )
    (net (code "79") (name "unconnected-(U2-Pad22)") (class "Default")
      (node (ref "U2") (pin "22") (pinfunction "22_22") (pintype "unspecified+no_connect"))
    )
    (net (code "80") (name "unconnected-(U2-Pad23)") (class "Default")
      (node (ref "U2") (pin "23") (pinfunction "23_23") (pintype "unspecified+no_connect"))
    )
    (net (code "81") (name "unconnected-(U2-Pad24)") (class "Default")
      (node (ref "U2") (pin "24") (pinfunction "24_24") (pintype "unspecified+no_connect"))
    )
    (net (code "82") (name "unconnected-(U2-Pad25)") (class "Default")
      (node (ref "U2") (pin "25") (pinfunction "25_25") (pintype "unspecified+no_connect"))
    )
    (net (code "83") (name "unconnected-(U2-Pad26)") (class "Default")
      (node (ref "U2") (pin "26") (pinfunction "26_26") (pintype "unspecified+no_connect"))
    )
    (net (code "84") (name "unconnected-(U2-Pad27)") (class "Default")
      (node (ref "U2") (pin "27") (pinfunction "27_27") (pintype "unspecified+no_connect"))
    )
    (net (code "85") (name "unconnected-(U2-Pad28)") (class "Default")
      (node (ref "U2") (pin "28") (pinfunction "28_28") (pintype "unspecified+no_connect"))
    )
    (net (code "86") (name "unconnected-(U2-Pad29)") (class "Default")
      (node (ref "U2") (pin "29") (pinfunction "29_29") (pintype "unspecified+no_connect"))
    )
    (net (code "87") (name "unconnected-(U2-Pad30)") (class "Default")
      (node (ref "U2") (pin "30") (pinfunction "30_30") (pintype "unspecified+no_connect"))
    )
    (net (code "88") (name "unconnected-(U2-Pad31)") (class "Default")
      (node (ref "U2") (pin "31") (pinfunction "31_31") (pintype "unspecified+no_connect"))
    )
    (net (code "89") (name "unconnected-(U2-Pad32)") (class "Default")
      (node (ref "U2") (pin "32") (pinfunction "32_32") (pintype "unspecified+no_connect"))
    )
    (net (code "90") (name "unconnected-(U2-Pad33)") (class "Default")
      (node (ref "U2") (pin "33") (pinfunction "33_33") (pintype "unspecified+no_connect"))
    )
    (net (code "91") (name "unconnected-(U2-Pad34)") (class "Default")
      (node (ref "U2") (pin "34") (pinfunction "34_34") (pintype "unspecified+no_connect"))
    )
    (net (code "92") (name "unconnected-(U2-Pad35)") (class "Default")
      (node (ref "U2") (pin "35") (pinfunction "35_35") (pintype "unspecified+no_connect"))
    )
    (net (code "93") (name "unconnected-(U2-Pad36)") (class "Default")
      (node (ref "U2") (pin "36") (pinfunction "36_36") (pintype "unspecified+no_connect"))
    )
    (net (code "94") (name "unconnected-(U3-Pad1)") (class "Default")
      (node (ref "U3") (pin "1") (pinfunction "1_1") (pintype "unspecified+no_connect"))
    )
    (net (code "95") (name "unconnected-(U3-Pad2)") (class "Default")
      (node (ref "U3") (pin "2") (pinfunction "2_2") (pintype "unspecified+no_connect"))
    )
    (net (code "96") (name "unconnected-(U3-Pad4)") (class "Default")
      (node (ref "U3") (pin "4") (pinfunction "4_4") (pintype "unspecified+no_connect"))
    )
    (net (code "97") (name "unconnected-(U3-Pad5)") (class "Default")
      (node (ref "U3") (pin "5") (pinfunction "5_5") (pintype "unspecified+no_connect"))
    )
    (net (code "98") (name "unconnected-(U3-Pad7)") (class "Default")
      (node (ref "U3") (pin "7") (pinfunction "7_7") (pintype "unspecified+no_connect"))
    )
    (net (code "99") (name "unconnected-(U3-Pad8)") (class "Default")
      (node (ref "U3") (pin "8") (pinfunction "8_8") (pintype "unspecified+no_connect"))
    )
    (net (code "100") (name "unconnected-(U3-Pad10)") (class "Default")
      (node (ref "U3") (pin "10") (pinfunction "10_10") (pintype "unspecified+no_connect"))
    )
    (net (code "101") (name "unconnected-(U3-Pad12)") (class "Default")
      (node (ref "U3") (pin "12") (pinfunction "12_12") (pintype "unspecified+no_connect"))
    )
    (net (code "102") (name "unconnected-(U3-Pad13)") (class "Default")
      (node (ref "U3") (pin "13") (pinfunction "13_13") (pintype "unspecified+no_connect"))
    )
    (net (code "103") (name "unconnected-(U3-Pad14)") (class "Default")
      (node (ref "U3") (pin "14") (pinfunction "14_14") (pintype "unspecified+no_connect"))
    )
    (net (code "104") (name "unconnected-(U3-Pad15)") (class "Default")
      (node (ref "U3") (pin "15") (pinfunction "15_15") (pintype "unspecified+no_connect"))
    )
    (net (code "105") (name "unconnected-(U3-Pad16)") (class "Default")
      (node (ref "U3") (pin "16") (pinfunction "16_16") (pintype "unspecified+no_connect"))
    )
    (net (code "106") (name "unconnected-(U3-Pad17)") (class "Default")
      (node (ref "U3") (pin "17") (pinfunction "17_17") (pintype "unspecified+no_connect"))
    )
    (net (code "107") (name "unconnected-(U3-Pad18)") (class "Default")
      (node (ref "U3") (pin "18") (pinfunction "18_18") (pintype "unspecified+no_connect"))
    )
    (net (code "108") (name "unconnected-(U3-Pad20)") (class "Default")
      (node (ref "U3") (pin "20") (pinfunction "20_20") (pintype "unspecified+no_connect"))
    )
    (net (code "109") (name "unconnected-(U3-Pad22)") (class "Default")
      (node (ref "U3") (pin "22") (pinfunction "22_22") (pintype "unspecified+no_connect"))
    )
    (net (code "110") (name "unconnected-(U3-Pad23)") (class "Default")
      (node (ref "U3") (pin "23") (pinfunction "23_23") (pintype "unspecified+no_connect"))
    )
    (net (code "111") (name "unconnected-(U3-Pad24)") (class "Default")
      (node (ref "U3") (pin "24") (pinfunction "24_24") (pintype "unspecified+no_connect"))
    )
    (net (code "112") (name "unconnected-(U3-Pad25)") (class "Default")
      (node (ref "U3") (pin "25") (pinfunction "25_25") (pintype "unspecified+no_connect"))
    )
    (net (code "113") (name "unconnected-(U3-Pad26)") (class "Default")
      (node (ref "U3") (pin "26") (pinfunction "26_26") (pintype "unspecified+no_connect"))
    )
    (net (code "114") (name "unconnected-(U3-Pad27)") (class "Default")
      (node (ref "U3") (pin "27") (pinfunction "27_27") (pintype "unspecified+no_connect"))
    )
    (net (code "115") (name "unconnected-(U3-Pad29)") (class "Default")
      (node (ref "U3") (pin "29") (pinfunction "29_29") (pintype "unspecified+no_connect"))
    )
    (net (code "116") (name "unconnected-(U3-Pad30)") (class "Default")
      (node (ref "U3") (pin "30") (pinfunction "30_30") (pintype "unspecified+no_connect"))
    )
    (net (code "117") (name "unconnected-(U3-Pad31)") (class "Default")
      (node (ref "U3") (pin "31") (pinfunction "31_31") (pintype "unspecified+no_connect"))
    )
    (net (code "118") (name "unconnected-(U3-Pad32)") (class "Default")
      (node (ref "U3") (pin "32") (pinfunction "32_32") (pintype "unspecified+no_connect"))
    )
    (net (code "119") (name "unconnected-(U3-Pad33)") (class "Default")
      (node (ref "U3") (pin "33") (pinfunction "33_33") (pintype "unspecified+no_connect"))
    )
    (net (code "120") (name "unconnected-(U3-Pad34)") (class "Default")
      (node (ref "U3") (pin "34") (pinfunction "34_34") (pintype "unspecified+no_connect"))
    )
    (net (code "121") (name "unconnected-(U3-Pad35)") (class "Default")
      (node (ref "U3") (pin "35") (pinfunction "35_35") (pintype "unspecified+no_connect"))
    )
    (net (code "122") (name "unconnected-(U3-Pad36)") (class "Default")
      (node (ref "U3") (pin "36") (pinfunction "36_36") (pintype "unspecified+no_connect"))
    )
    (net (code "123") (name "unconnected-(U3-Pad37)") (class "Default")
      (node (ref "U3") (pin "37") (pinfunction "37_37") (pintype "unspecified+no_connect"))
    )
    (net (code "124") (name "unconnected-(U3-Pad38)") (class "Default")
      (node (ref "U3") (pin "38") (pinfunction "38_38") (pintype "unspecified+no_connect"))
    )
    (net (code "125") (name "unconnected-(U3-Pad39)") (class "Default")
      (node (ref "U3") (pin "39") (pinfunction "39_39") (pintype "unspecified+no_connect"))
    )
    (net (code "126") (name "unconnected-(U3-Pad40)") (class "Default")
      (node (ref "U3") (pin "40") (pinfunction "40_40") (pintype "unspecified+no_connect"))
    )
    (net (code "127") (name "unconnected-(U4-Pad1)") (class "Default")
      (node (ref "U4") (pin "1") (pinfunction "1_1") (pintype "unspecified+no_connect"))
    )
    (net (code "128") (name "unconnected-(U4-Pad2)") (class "Default")
      (node (ref "U4") (pin "2") (pinfunction "2_2") (pintype "unspecified+no_connect"))
    )
    (net (code "129") (name "unconnected-(U4-Pad3)") (class "Default")
      (node (ref "U4") (pin "3") (pinfunction "3_3") (pintype "unspecified+no_connect"))
    )
    (net (code "130") (name "unconnected-(U4-Pad4)") (class "Default")
      (node (ref "U4") (pin "4") (pinfunction "4_4") (pintype "unspecified+no_connect"))
    )
    (net (code "131") (name "unconnected-(U4-Pad5)") (class "Default")
      (node (ref "U4") (pin "5") (pinfunction "5_5") (pintype "unspecified+no_connect"))
    )
    (net (code "132") (name "unconnected-(U4-Pad6)") (class "Default")
      (node (ref "U4") (pin "6") (pinfunction "6_6") (pintype "unspecified+no_connect"))
    )
    (net (code "133") (name "unconnected-(U4-Pad7)") (class "Default")
      (node (ref "U4") (pin "7") (pinfunction "7_7") (pintype "unspecified+no_connect"))
    )
    (net (code "134") (name "unconnected-(U4-Pad8)") (class "Default")
      (node (ref "U4") (pin "8") (pinfunction "8_8") (pintype "unspecified+no_connect"))
    )
    (net (code "135") (name "unconnected-(U5-Pad1)") (class "Default")
      (node (ref "U5") (pin "1") (pinfunction "1_1") (pintype "unspecified+no_connect"))
    )
    (net (code "136") (name "unconnected-(U5-Pad2)") (class "Default")
      (node (ref "U5") (pin "2") (pinfunction "2_2") (pintype "unspecified+no_connect"))
    )
    (net (code "137") (name "unconnected-(U5-Pad3)") (class "Default")
      (node (ref "U5") (pin "3") (pinfunction "3_3") (pintype "unspecified+no_connect"))
    )
    (net (code "138") (name "unconnected-(U5-Pad4)") (class "Default")
      (node (ref "U5") (pin "4") (pinfunction "4_4") (pintype "unspecified+no_connect"))
    )
    (net (code "139") (name "unconnected-(U5-Pad5)") (class "Default")
      (node (ref "U5") (pin "5") (pinfunction "5_5") (pintype "unspecified+no_connect"))
    )
    (net (code "140") (name "unconnected-(U5-Pad6)") (class "Default")
      (node (ref "U5") (pin "6") (pinfunction "6_6") (pintype "unspecified+no_connect"))
    )
    (net (code "141") (name "unconnected-(U5-Pad7)") (class "Default")
      (node (ref "U5") (pin "7") (pinfunction "7_7") (pintype "unspecified+no_connect"))
    )
    (net (code "142") (name "unconnected-(U5-Pad8)") (class "Default")
      (node (ref "U5") (pin "8") (pinfunction "8_8") (pintype "unspecified+no_connect"))
    )
    (net (code "143") (name "unconnected-(U6-NC-Pad4)") (class "Default")
      (node (ref "U6") (pin "4") (pinfunction "NC_4") (pintype "unspecified+no_connect"))
    )
    (net (code "144") (name "unconnected-(U8-CTS#-Pad9)") (class "Default")
      (node (ref "U8") (pin "9") (pinfunction "CTS#_9") (pintype "input+no_connect"))
    )
    (net (code "145") (name "unconnected-(U8-DCD#-Pad12)") (class "Default")
      (node (ref "U8") (pin "12") (pinfunction "DCD#_12") (pintype "input+no_connect"))
    )
    (net (code "146") (name "unconnected-(U8-DSR#-Pad10)") (class "Default")
      (node (ref "U8") (pin "10") (pinfunction "DSR#_10") (pintype "input+no_connect"))
    )
    (net (code "147") (name "unconnected-(U8-DTR#-Pad13)") (class "Default")
      (node (ref "U8") (pin "13") (pinfunction "DTR#_13") (pintype "input+no_connect"))
    )
    (net (code "148") (name "unconnected-(U8-R232-Pad15)") (class "Default")
      (node (ref "U8") (pin "15") (pinfunction "R232_15") (pintype "input+no_connect"))
    )
    (net (code "149") (name "unconnected-(U8-RI#-Pad11)") (class "Default")
      (node (ref "U8") (pin "11") (pinfunction "RI#_11") (pintype "input+no_connect"))
    )
    (net (code "150") (name "unconnected-(U8-RTS#-Pad14)") (class "Default")
      (node (ref "U8") (pin "14") (pinfunction "RTS#_14") (pintype "input+no_connect"))
    )
    (net (code "151") (name "unconnected-(USB1-SBU1-Pad9)") (class "Default")
      (node (ref "USB1") (pin "9") (pinfunction "SBU1_9") (pintype "input+no_connect"))
    )
    (net (code "152") (name "unconnected-(USB1-SBU2-Pad3)") (class "Default")
      (node (ref "USB1") (pin "3") (pinfunction "SBU2_3") (pintype "input+no_connect"))
    )
  )
)
